# eagle_cad_tutorial_rob.net
KiCad netlist of a schematic drawn in EAGLE
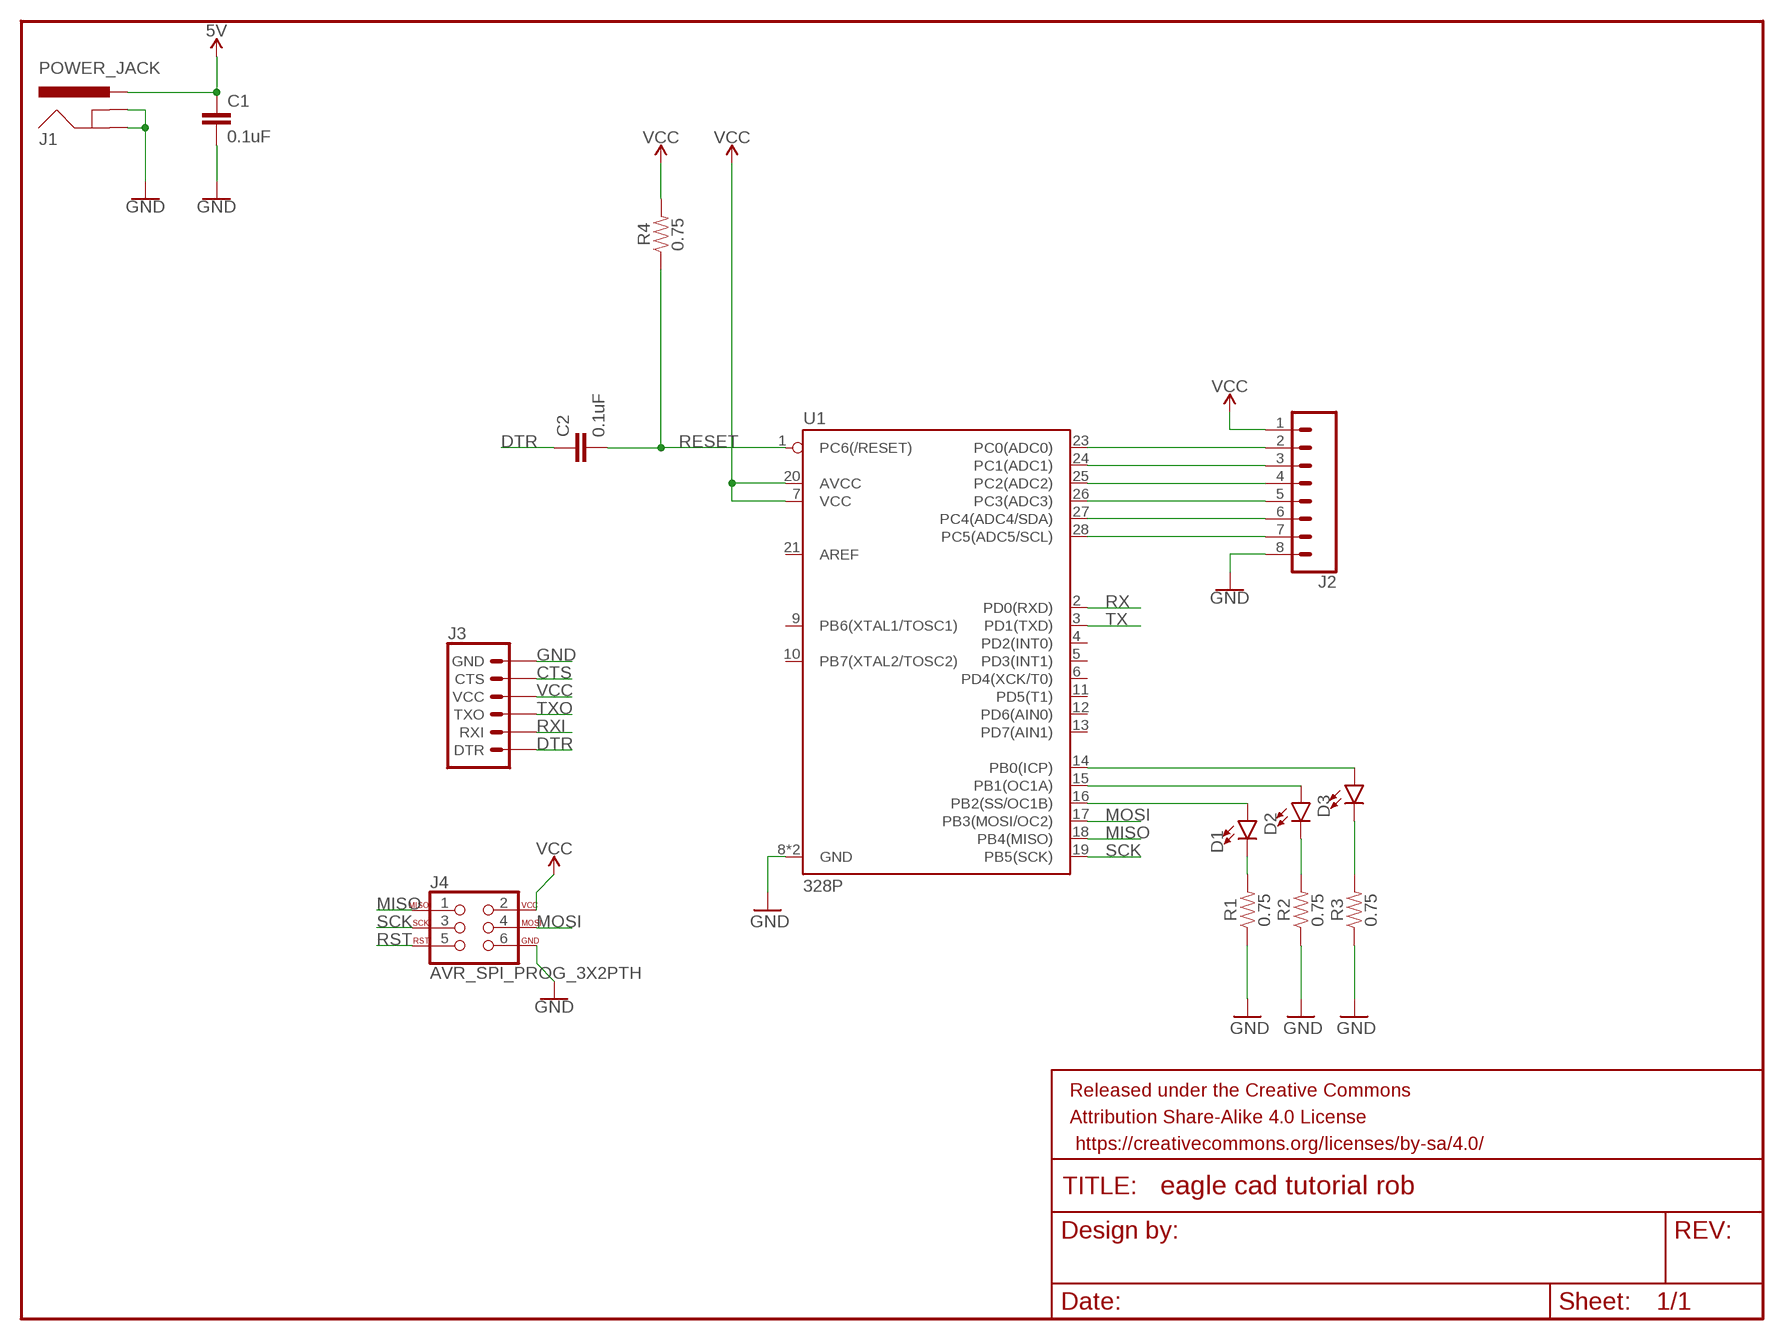
[diagram p0: schematic, sheet 1]

(export (version "E")
  (design (tool "Eeschema 10.0.6"))
  (components
    (comp (ref "C1")
      (value "0.1uF")
      (footprint "eagle-import:0402")
      (libsource (lib "eagle-import") (part "0.1UF-0402-16V-10%"))
    )
    (comp (ref "C2")
      (value "0.1uF")
      (footprint "eagle-import:0603")
      (libsource (lib "eagle-import") (part "0.1UF-0603-25V-(+80/-20%)"))
    )
    (comp (ref "D1")
      (value "LED5MM")
      (footprint "eagle-import:LED_5MM")
      (libsource (lib "eagle-import") (part "LED5MM"))
    )
    (comp (ref "D2")
      (value "LED5MM")
      (footprint "eagle-import:LED_5MM")
      (libsource (lib "eagle-import") (part "LED5MM"))
    )
    (comp (ref "D3")
      (value "LED5MM")
      (footprint "eagle-import:LED_5MM")
      (libsource (lib "eagle-import") (part "LED5MM"))
    )
    (comp (ref "FRAME1")
      (value "FRAME-LETTER")
      (footprint "eagle-import:CREATIVE_COMMONS")
      (libsource (lib "eagle-import") (part "FRAME-LETTER"))
    )
    (comp (ref "J1")
      (value "POWER_JACK")
      (footprint "eagle-import:POWER_JACK_PTH")
      (libsource (lib "eagle-import") (part "POWER_JACK"))
    )
    (comp (ref "J2")
      (value "CONN_08\"")
      (footprint "eagle-import:1X08")
      (libsource (lib "eagle-import") (part "CONN_08{dblquote}"))
    )
    (comp (ref "J3")
      (value "6_PIN_SERIAL_TARGETSILK")
      (footprint "eagle-import:6_PIN_SERIAL_TARGET_SIDE_W_SILK")
      (libsource (lib "eagle-import") (part "6_PIN_SERIAL_TARGETSILK"))
    )
    (comp (ref "J4")
      (value "AVR_SPI_PROG_3X2PTH")
      (footprint "eagle-import:2X3")
      (libsource (lib "eagle-import") (part "AVR_SPI_PROG_3X2PTH"))
    )
    (comp (ref "R1")
      (value "0.75")
      (footprint "eagle-import:0805")
      (libsource (lib "eagle-import") (part "0.75OHM-0805-1/4W-1%"))
    )
    (comp (ref "R2")
      (value "0.75")
      (footprint "eagle-import:0805")
      (libsource (lib "eagle-import") (part "0.75OHM-0805-1/4W-1%"))
    )
    (comp (ref "R3")
      (value "0.75")
      (footprint "eagle-import:0805")
      (libsource (lib "eagle-import") (part "0.75OHM-0805-1/4W-1%"))
    )
    (comp (ref "R4")
      (value "0.75")
      (footprint "eagle-import:0805")
      (libsource (lib "eagle-import") (part "0.75OHM-0805-1/4W-1%"))
    )
    (comp (ref "U1")
      (value "328P")
      (footprint "eagle-import:DIP28")
      (libsource (lib "eagle-import") (part "ATMEGA328P_PDIP"))
    )
  )
  (nets
    (net (code "1") (name "/CTS") (class "Default")
      (node (ref "J3") (pin "P$5") (pinfunction "CTS_P$5") (pintype "passive"))
    )
    (net (code "2") (name "/DTR") (class "Default")
      (node (ref "C2") (pin "1") (pinfunction "1_1") (pintype "passive"))
      (node (ref "J3") (pin "P$1") (pinfunction "DTR_P$1") (pintype "passive"))
    )
    (net (code "3") (name "/MISO") (class "Default")
      (node (ref "J4") (pin "1") (pinfunction "1_1") (pintype "passive"))
      (node (ref "U1") (pin "18") (pinfunction "PB4(MISO)_18") (pintype "bidirectional"))
    )
    (net (code "4") (name "/MOSI") (class "Default")
      (node (ref "J4") (pin "4") (pinfunction "4_4") (pintype "passive"))
      (node (ref "U1") (pin "17") (pinfunction "PB3(MOSI/OC2)_17") (pintype "bidirectional"))
    )
    (net (code "5") (name "/RESET") (class "Default")
      (node (ref "C2") (pin "2") (pinfunction "2_2") (pintype "passive"))
      (node (ref "R4") (pin "1") (pinfunction "1_1") (pintype "passive"))
      (node (ref "U1") (pin "1") (pinfunction "PC6(/RESET)_1") (pintype "bidirectional"))
    )
    (net (code "6") (name "/RST") (class "Default")
      (node (ref "J4") (pin "5") (pinfunction "5_5") (pintype "passive"))
    )
    (net (code "7") (name "/RX") (class "Default")
      (node (ref "U1") (pin "2") (pinfunction "PD0(RXD)_2") (pintype "bidirectional"))
    )
    (net (code "8") (name "/RXI") (class "Default")
      (node (ref "J3") (pin "P$3") (pinfunction "RXI_P$3") (pintype "passive"))
    )
    (net (code "9") (name "/SCK") (class "Default")
      (node (ref "J4") (pin "3") (pinfunction "3_3") (pintype "passive"))
      (node (ref "U1") (pin "19") (pinfunction "PB5(SCK)_19") (pintype "bidirectional"))
    )
    (net (code "10") (name "/TX") (class "Default")
      (node (ref "U1") (pin "3") (pinfunction "PD1(TXD)_3") (pintype "bidirectional"))
    )
    (net (code "11") (name "/TXO") (class "Default")
      (node (ref "J3") (pin "P$2") (pinfunction "TXO_P$2") (pintype "passive"))
    )
    (net (code "12") (name "5V") (class "Default")
      (node (ref "C1") (pin "1") (pinfunction "1_1") (pintype "passive"))
      (node (ref "J1") (pin "PWR") (pinfunction "PWR_PWR") (pintype "bidirectional"))
    )
    (net (code "13") (name "GND") (class "Default")
      (node (ref "C1") (pin "2") (pinfunction "2_2") (pintype "passive"))
      (node (ref "J1") (pin "GND") (pinfunction "GND_GND") (pintype "bidirectional"))
      (node (ref "J1") (pin "GNDBREAK") (pinfunction "GNDBREAK_GNDBREAK") (pintype "bidirectional"))
      (node (ref "J2") (pin "8") (pinfunction "8_8") (pintype "passive"))
      (node (ref "J3") (pin "P$6") (pinfunction "GND_P$6") (pintype "passive"))
      (node (ref "J4") (pin "6") (pinfunction "6_6") (pintype "passive"))
      (node (ref "R1") (pin "1") (pinfunction "1_1") (pintype "passive"))
      (node (ref "R2") (pin "1") (pinfunction "1_1") (pintype "passive"))
      (node (ref "R3") (pin "1") (pinfunction "1_1") (pintype "passive"))
      (node (ref "U1") (pin "22") (pinfunction "GND_22") (pintype "bidirectional"))
      (node (ref "U1") (pin "8") (pinfunction "GND_8") (pintype "bidirectional"))
    )
    (net (code "14") (name "Net-(D1-C)") (class "Default")
      (node (ref "D1") (pin "K") (pinfunction "C_K") (pintype "passive"))
      (node (ref "R1") (pin "2") (pinfunction "2_2") (pintype "passive"))
    )
    (net (code "15") (name "Net-(D2-C)") (class "Default")
      (node (ref "D2") (pin "K") (pinfunction "C_K") (pintype "passive"))
      (node (ref "R2") (pin "2") (pinfunction "2_2") (pintype "passive"))
    )
    (net (code "16") (name "Net-(D3-C)") (class "Default")
      (node (ref "D3") (pin "K") (pinfunction "C_K") (pintype "passive"))
      (node (ref "R3") (pin "2") (pinfunction "2_2") (pintype "passive"))
    )
    (net (code "17") (name "Net-(U1-PB0(ICP))") (class "Default")
      (node (ref "D3") (pin "A") (pinfunction "A_A") (pintype "passive"))
      (node (ref "U1") (pin "14") (pinfunction "PB0(ICP)_14") (pintype "bidirectional"))
    )
    (net (code "18") (name "Net-(U1-PB1(OC1A))") (class "Default")
      (node (ref "D2") (pin "A") (pinfunction "A_A") (pintype "passive"))
      (node (ref "U1") (pin "15") (pinfunction "PB1(OC1A)_15") (pintype "bidirectional"))
    )
    (net (code "19") (name "Net-(U1-PB2(SS{slash}OC1B))") (class "Default")
      (node (ref "D1") (pin "A") (pinfunction "A_A") (pintype "passive"))
      (node (ref "U1") (pin "16") (pinfunction "PB2(SS/OC1B)_16") (pintype "bidirectional"))
    )
    (net (code "20") (name "Net-(U1-PC0(ADC0))") (class "Default")
      (node (ref "J2") (pin "2") (pinfunction "2_2") (pintype "passive"))
      (node (ref "U1") (pin "23") (pinfunction "PC0(ADC0)_23") (pintype "bidirectional"))
    )
    (net (code "21") (name "Net-(U1-PC1(ADC1))") (class "Default")
      (node (ref "J2") (pin "3") (pinfunction "3_3") (pintype "passive"))
      (node (ref "U1") (pin "24") (pinfunction "PC1(ADC1)_24") (pintype "bidirectional"))
    )
    (net (code "22") (name "Net-(U1-PC2(ADC2))") (class "Default")
      (node (ref "J2") (pin "4") (pinfunction "4_4") (pintype "passive"))
      (node (ref "U1") (pin "25") (pinfunction "PC2(ADC2)_25") (pintype "bidirectional"))
    )
    (net (code "23") (name "Net-(U1-PC3(ADC3))") (class "Default")
      (node (ref "J2") (pin "5") (pinfunction "5_5") (pintype "passive"))
      (node (ref "U1") (pin "26") (pinfunction "PC3(ADC3)_26") (pintype "bidirectional"))
    )
    (net (code "24") (name "Net-(U1-PC4(ADC4{slash}SDA))") (class "Default")
      (node (ref "J2") (pin "6") (pinfunction "6_6") (pintype "passive"))
      (node (ref "U1") (pin "27") (pinfunction "PC4(ADC4/SDA)_27") (pintype "bidirectional"))
    )
    (net (code "25") (name "Net-(U1-PC5(ADC5{slash}SCL))") (class "Default")
      (node (ref "J2") (pin "7") (pinfunction "7_7") (pintype "passive"))
      (node (ref "U1") (pin "28") (pinfunction "PC5(ADC5/SCL)_28") (pintype "bidirectional"))
    )
    (net (code "26") (name "VCC") (class "Default")
      (node (ref "J2") (pin "1") (pinfunction "1_1") (pintype "passive"))
      (node (ref "J3") (pin "P$4") (pinfunction "VCC_P$4") (pintype "passive"))
      (node (ref "J4") (pin "2") (pinfunction "2_2") (pintype "passive"))
      (node (ref "R4") (pin "2") (pinfunction "2_2") (pintype "passive"))
      (node (ref "U1") (pin "20") (pinfunction "AVCC_20") (pintype "bidirectional"))
      (node (ref "U1") (pin "7") (pinfunction "VCC_7") (pintype "bidirectional"))
    )
    (net (code "27") (name "unconnected-(U1-AREF-Pad21)") (class "Default")
      (node (ref "U1") (pin "21") (pinfunction "AREF_21") (pintype "bidirectional"))
    )
    (net (code "28") (name "unconnected-(U1-PB6(XTAL1{slash}TOSC1)-Pad9)") (class "Default")
      (node (ref "U1") (pin "9") (pinfunction "PB6(XTAL1/TOSC1)_9") (pintype "bidirectional"))
    )
    (net (code "29") (name "unconnected-(U1-PB7(XTAL2{slash}TOSC2)-Pad10)") (class "Default")
      (node (ref "U1") (pin "10") (pinfunction "PB7(XTAL2/TOSC2)_10") (pintype "bidirectional"))
    )
    (net (code "30") (name "unconnected-(U1-PD2(INT0)-Pad4)") (class "Default")
      (node (ref "U1") (pin "4") (pinfunction "PD2(INT0)_4") (pintype "bidirectional"))
    )
    (net (code "31") (name "unconnected-(U1-PD3(INT1)-Pad5)") (class "Default")
      (node (ref "U1") (pin "5") (pinfunction "PD3(INT1)_5") (pintype "bidirectional"))
    )
    (net (code "32") (name "unconnected-(U1-PD4(XCK{slash}T0)-Pad6)") (class "Default")
      (node (ref "U1") (pin "6") (pinfunction "PD4(XCK/T0)_6") (pintype "bidirectional"))
    )
    (net (code "33") (name "unconnected-(U1-PD5(T1)-Pad11)") (class "Default")
      (node (ref "U1") (pin "11") (pinfunction "PD5(T1)_11") (pintype "bidirectional"))
    )
    (net (code "34") (name "unconnected-(U1-PD6(AIN0)-Pad12)") (class "Default")
      (node (ref "U1") (pin "12") (pinfunction "PD6(AIN0)_12") (pintype "bidirectional"))
    )
    (net (code "35") (name "unconnected-(U1-PD7(AIN1)-Pad13)") (class "Default")
      (node (ref "U1") (pin "13") (pinfunction "PD7(AIN1)_13") (pintype "bidirectional"))
    )
  )
)
